# 201944AEP4P03.net
KiCad netlist of a schematic drawn in Altium Designer
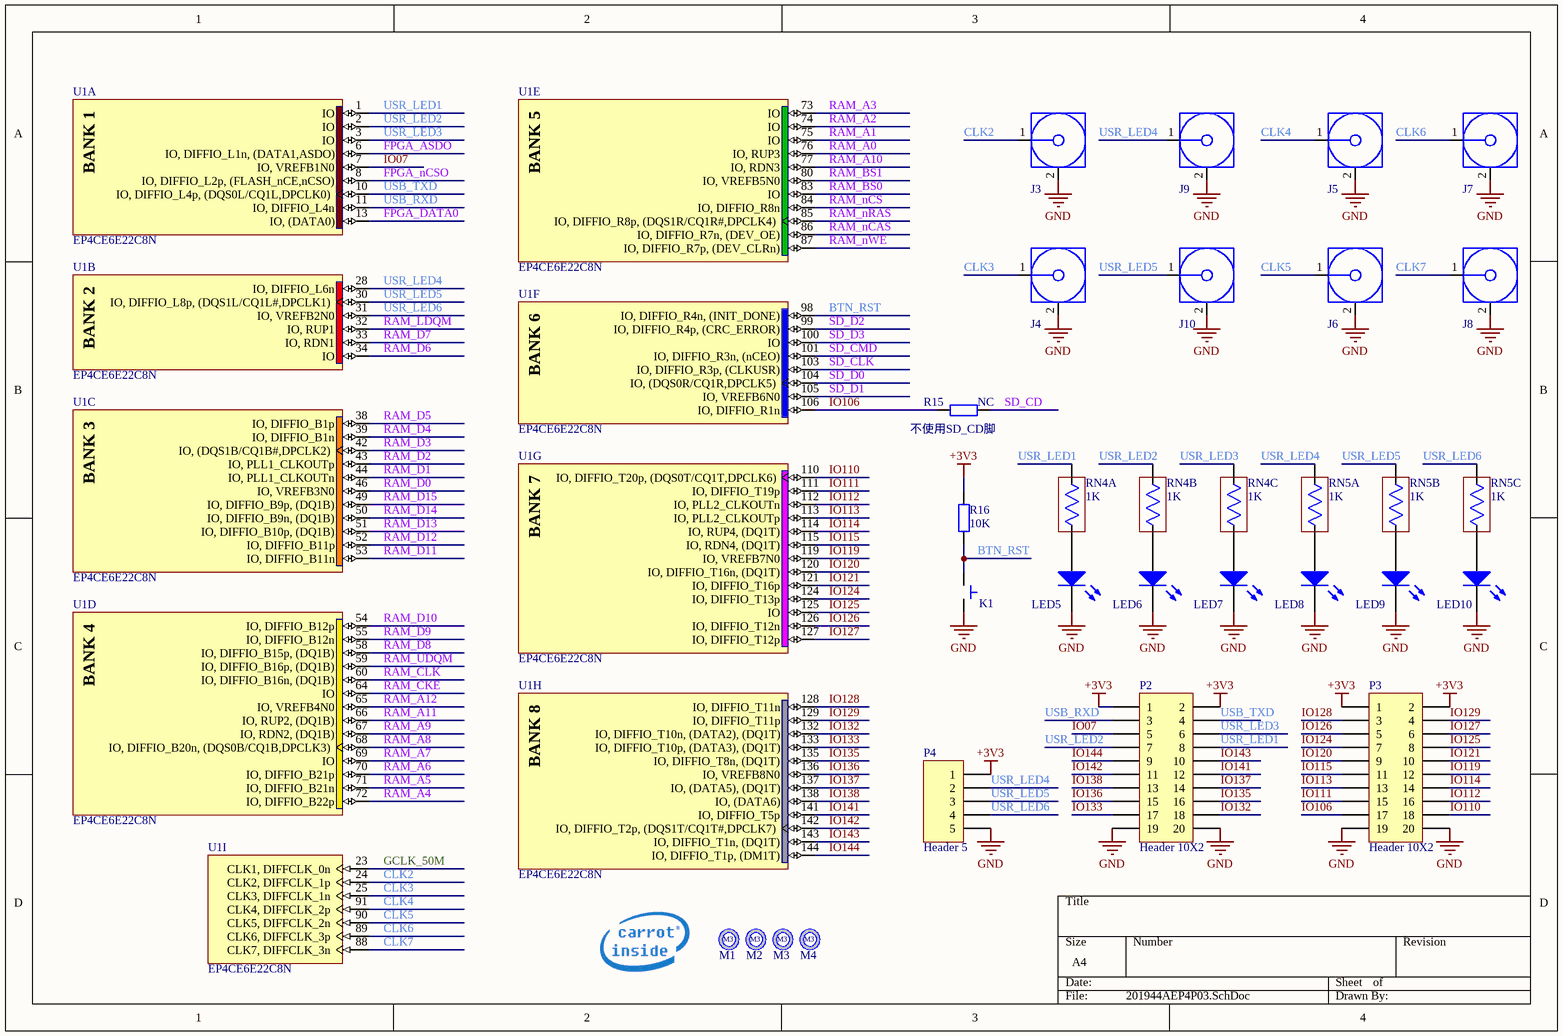
[diagram p0: 201944AEP4P03.SchDoc]

(export (version "E")
  (design (tool "Eeschema 10.0.6"))
  (components
    (comp (ref "J3") (value "SMA") (footprint "SMA-1") (libsource (lib "carrot_lib") (part "SMA")))
    (comp (ref "J4") (value "SMA") (footprint "SMA-1") (libsource (lib "carrot_lib") (part "SMA")))
    (comp (ref "J5") (value "SMA") (footprint "SMA-1") (libsource (lib "carrot_lib") (part "SMA")))
    (comp (ref "J6") (value "SMA") (footprint "SMA-1") (libsource (lib "carrot_lib") (part "SMA")))
    (comp (ref "J7") (value "SMA") (footprint "SMA-1") (libsource (lib "carrot_lib") (part "SMA")))
    (comp (ref "J8") (value "SMA") (footprint "SMA-1") (libsource (lib "carrot_lib") (part "SMA")))
    (comp (ref "J9") (value "SMA") (footprint "SMA-1") (libsource (lib "carrot_lib") (part "SMA")))
    (comp (ref "J10") (value "SMA") (footprint "SMA-1") (libsource (lib "carrot_lib") (part "SMA")))
    (comp (ref "K1")
      (value "轻触开关")
      (footprint "Button-SMT-Small")
      (libsource (lib "carrot_lib") (part "Button"))
    )
    (comp (ref "LED5") (value "LED") (footprint "LED1206") (libsource (lib "carrot_lib") (part "LED")))
    (comp (ref "LED6") (value "LED") (footprint "LED1206") (libsource (lib "carrot_lib") (part "LED")))
    (comp (ref "LED7") (value "LED") (footprint "LED1206") (libsource (lib "carrot_lib") (part "LED")))
    (comp (ref "LED8") (value "LED") (footprint "LED1206") (libsource (lib "carrot_lib") (part "LED")))
    (comp (ref "LED9") (value "LED") (footprint "LED1206") (libsource (lib "carrot_lib") (part "LED")))
    (comp (ref "LED10") (value "LED") (footprint "LED1206") (libsource (lib "carrot_lib") (part "LED")))
    (comp (ref "LOGO1")
      (value "Logo Carrot Inside")
      (footprint "LOGO-carrot-inside")
      (libsource (lib "carrot_lib") (part "Logo Carrot Inside"))
    )
    (comp (ref "M1") (value "M3") (footprint "M3-3.2X5") (libsource (lib "carrot_lib") (part "M3")))
    (comp (ref "M2") (value "M3") (footprint "M3-3.2X5") (libsource (lib "carrot_lib") (part "M3")))
    (comp (ref "M3") (value "M3") (footprint "M3-3.2X5") (libsource (lib "carrot_lib") (part "M3")))
    (comp (ref "M4") (value "M3") (footprint "M3-3.2X5") (libsource (lib "carrot_lib") (part "M3")))
    (comp (ref "P2")
      (value "Header 10X2")
      (footprint "HDR2X10")
      (description "Header, 10-Pin, Dual row")
      (fields (field (name "PUBLISHER") "Altium Limited"))
      (libsource (lib "Miscellaneous Connectors") (part "Header 10X2"))
    )
    (comp (ref "P3")
      (value "Header 10X2")
      (footprint "HDR2X10")
      (description "Header, 10-Pin, Dual row")
      (fields (field (name "PUBLISHER") "Altium Limited"))
      (libsource (lib "Miscellaneous Connectors") (part "Header 10X2"))
    )
    (comp (ref "P4")
      (value "Header 5")
      (footprint "HDR1X5")
      (description "Header, 5-Pin")
      (fields (field (name "PUBLISHER") "Altium Limited"))
      (libsource (lib "Miscellaneous Connectors") (part "Header 5"))
    )
    (comp (ref "R15")
      (value "NC")
      (footprint "R0805")
      (fields (field (name "Comment") "Res"))
      (libsource (lib "carrot_lib") (part "Res"))
    )
    (comp (ref "R16")
      (value "10K")
      (footprint "R0805")
      (fields (field (name "Comment") "Res"))
      (libsource (lib "") (part "Res_1"))
    )
    (comp (ref "RN4")
      (value "1K")
      (footprint "RA0603")
      (description "贴片排阻")
      (fields (field (name "Comment") "Res Array"))
      (libsource (lib "carrot_lib") (part "Res Array 2"))
    )
    (comp (ref "RN5")
      (value "1K")
      (footprint "RA0603")
      (description "贴片排阻")
      (fields (field (name "Comment") "Res Array"))
      (libsource (lib "carrot_lib") (part "Res Array 2"))
    )
    (comp (ref "U1")
      (value "EP4CE6E22C8N")
      (footprint "EP4CE6E22C8N-EQFP144+")
      (fields (field (name "MANUFACTURER") "Altera"))
      (libsource (lib "") (part "EP4CE6E22C8N_1"))
    )
  )
  (nets
    (net (code "1") (name "+3V3") (class "Default")
      (node (ref "P2") (pin "1") (pinfunction "1_1") (pintype "passive"))
      (node (ref "P2") (pin "2") (pinfunction "2_2") (pintype "passive"))
      (node (ref "P3") (pin "1") (pinfunction "1_1") (pintype "passive"))
      (node (ref "P3") (pin "2") (pinfunction "2_2") (pintype "passive"))
      (node (ref "P4") (pin "1") (pinfunction "1_1") (pintype "passive"))
      (node (ref "R16") (pin "1") (pinfunction "1_1") (pintype "passive"))
    )
    (net (code "2") (name "/BTN_RST") (class "Default")
      (node (ref "K1") (pin "1") (pinfunction "IN_1") (pintype "passive"))
      (node (ref "R16") (pin "2") (pinfunction "2_2") (pintype "passive"))
      (node (ref "U1") (pin "98") (pinfunction "IO,_DIFFIO_R4n,_(INIT_DONE)_98") (pintype "bidirectional"))
    )
    (net (code "3") (name "/CLK2") (class "Default")
      (node (ref "J3") (pin "1") (pinfunction "Signal_1") (pintype "power_in"))
      (node (ref "U1") (pin "24") (pinfunction "CLK2,_DIFFCLK_1p_24") (pintype "input"))
    )
    (net (code "4") (name "/CLK3") (class "Default")
      (node (ref "J4") (pin "1") (pinfunction "Signal_1") (pintype "power_in"))
      (node (ref "U1") (pin "25") (pinfunction "CLK3,_DIFFCLK_1n_25") (pintype "input"))
    )
    (net (code "5") (name "/CLK4") (class "Default")
      (node (ref "J5") (pin "1") (pinfunction "Signal_1") (pintype "power_in"))
      (node (ref "U1") (pin "91") (pinfunction "CLK4,_DIFFCLK_2p_91") (pintype "input"))
    )
    (net (code "6") (name "/CLK5") (class "Default")
      (node (ref "J6") (pin "1") (pinfunction "Signal_1") (pintype "power_in"))
      (node (ref "U1") (pin "90") (pinfunction "CLK5,_DIFFCLK_2n_90") (pintype "input"))
    )
    (net (code "7") (name "/CLK6") (class "Default")
      (node (ref "J7") (pin "1") (pinfunction "Signal_1") (pintype "power_in"))
      (node (ref "U1") (pin "89") (pinfunction "CLK6,_DIFFCLK_3p_89") (pintype "input"))
    )
    (net (code "8") (name "/CLK7") (class "Default")
      (node (ref "J8") (pin "1") (pinfunction "Signal_1") (pintype "power_in"))
      (node (ref "U1") (pin "88") (pinfunction "CLK7,_DIFFCLK_3n_88") (pintype "input"))
    )
    (net (code "9") (name "/FPGA_ASDO") (class "Default")
      (node (ref "U1") (pin "6") (pinfunction "IO,_DIFFIO_L1n,_(DATA1,ASDO)_6") (pintype "bidirectional"))
    )
    (net (code "10") (name "/FPGA_DATA0") (class "Default")
      (node (ref "U1") (pin "13") (pinfunction "IO,_(DATA0)_13") (pintype "bidirectional"))
    )
    (net (code "11") (name "/FPGA_nCSO") (class "Default")
      (node (ref "U1") (pin "8") (pinfunction "IO,_DIFFIO_L2p,_(FLASH_nCE,nCSO)_8") (pintype "bidirectional"))
    )
    (net (code "12") (name "/GCLK_50M") (class "Default")
      (node (ref "U1") (pin "23") (pinfunction "CLK1,_DIFFCLK_0n_23") (pintype "input"))
    )
    (net (code "13") (name "/IO07") (class "Default")
      (node (ref "P2") (pin "5") (pinfunction "5_5") (pintype "passive"))
      (node (ref "U1") (pin "7") (pinfunction "IO,_VREFB1N0_7") (pintype "bidirectional"))
    )
    (net (code "14") (name "/IO106") (class "Default")
      (node (ref "P3") (pin "17") (pinfunction "17_17") (pintype "passive"))
      (node (ref "R15") (pin "1") (pinfunction "1_1") (pintype "passive"))
      (node (ref "U1") (pin "106") (pinfunction "IO,_DIFFIO_R1n_106") (pintype "bidirectional"))
    )
    (net (code "15") (name "/IO110") (class "Default")
      (node (ref "P3") (pin "18") (pinfunction "18_18") (pintype "passive"))
      (node (ref "U1") (pin "110") (pinfunction "IO,_DIFFIO_T20p,_(DQS0T/CQ1T,DPCLK6)_110") (pintype "bidirectional"))
    )
    (net (code "16") (name "/IO111") (class "Default")
      (node (ref "P3") (pin "15") (pinfunction "15_15") (pintype "passive"))
      (node (ref "U1") (pin "111") (pinfunction "IO,_DIFFIO_T19p_111") (pintype "bidirectional"))
    )
    (net (code "17") (name "/IO112") (class "Default")
      (node (ref "P3") (pin "16") (pinfunction "16_16") (pintype "passive"))
      (node (ref "U1") (pin "112") (pinfunction "IO,_PLL2_CLKOUTn_112") (pintype "bidirectional"))
    )
    (net (code "18") (name "/IO113") (class "Default")
      (node (ref "P3") (pin "13") (pinfunction "13_13") (pintype "passive"))
      (node (ref "U1") (pin "113") (pinfunction "IO,_PLL2_CLKOUTp_113") (pintype "bidirectional"))
    )
    (net (code "19") (name "/IO114") (class "Default")
      (node (ref "P3") (pin "14") (pinfunction "14_14") (pintype "passive"))
      (node (ref "U1") (pin "114") (pinfunction "IO,_RUP4,_(DQ1T)_114") (pintype "bidirectional"))
    )
    (net (code "20") (name "/IO115") (class "Default")
      (node (ref "P3") (pin "11") (pinfunction "11_11") (pintype "passive"))
      (node (ref "U1") (pin "115") (pinfunction "IO,_RDN4,_(DQ1T)_115") (pintype "bidirectional"))
    )
    (net (code "21") (name "/IO119") (class "Default")
      (node (ref "P3") (pin "12") (pinfunction "12_12") (pintype "passive"))
      (node (ref "U1") (pin "119") (pinfunction "IO,_VREFB7N0_119") (pintype "bidirectional"))
    )
    (net (code "22") (name "/IO120") (class "Default")
      (node (ref "P3") (pin "9") (pinfunction "9_9") (pintype "passive"))
      (node (ref "U1") (pin "120") (pinfunction "IO,_DIFFIO_T16n,_(DQ1T)_120") (pintype "bidirectional"))
    )
    (net (code "23") (name "/IO121") (class "Default")
      (node (ref "P3") (pin "10") (pinfunction "10_10") (pintype "passive"))
      (node (ref "U1") (pin "121") (pinfunction "IO,_DIFFIO_T16p_121") (pintype "bidirectional"))
    )
    (net (code "24") (name "/IO124") (class "Default")
      (node (ref "P3") (pin "7") (pinfunction "7_7") (pintype "passive"))
      (node (ref "U1") (pin "124") (pinfunction "IO,_DIFFIO_T13p_124") (pintype "bidirectional"))
    )
    (net (code "25") (name "/IO125") (class "Default")
      (node (ref "P3") (pin "8") (pinfunction "8_8") (pintype "passive"))
      (node (ref "U1") (pin "125") (pinfunction "IO_125") (pintype "bidirectional"))
    )
    (net (code "26") (name "/IO126") (class "Default")
      (node (ref "P3") (pin "5") (pinfunction "5_5") (pintype "passive"))
      (node (ref "U1") (pin "126") (pinfunction "IO,_DIFFIO_T12n_126") (pintype "bidirectional"))
    )
    (net (code "27") (name "/IO127") (class "Default")
      (node (ref "P3") (pin "6") (pinfunction "6_6") (pintype "passive"))
      (node (ref "U1") (pin "127") (pinfunction "IO,_DIFFIO_T12p_127") (pintype "bidirectional"))
    )
    (net (code "28") (name "/IO128") (class "Default")
      (node (ref "P3") (pin "3") (pinfunction "3_3") (pintype "passive"))
      (node (ref "U1") (pin "128") (pinfunction "IO,_DIFFIO_T11n_128") (pintype "bidirectional"))
    )
    (net (code "29") (name "/IO129") (class "Default")
      (node (ref "P3") (pin "4") (pinfunction "4_4") (pintype "passive"))
      (node (ref "U1") (pin "129") (pinfunction "IO,_DIFFIO_T11p_129") (pintype "bidirectional"))
    )
    (net (code "30") (name "/IO132") (class "Default")
      (node (ref "P2") (pin "18") (pinfunction "18_18") (pintype "passive"))
      (node (ref "U1") (pin "132") (pinfunction "IO,_DIFFIO_T10n,_(DATA2),_(DQ1T)_132") (pintype "bidirectional"))
    )
    (net (code "31") (name "/IO133") (class "Default")
      (node (ref "P2") (pin "17") (pinfunction "17_17") (pintype "passive"))
      (node (ref "U1") (pin "133") (pinfunction "IO,_DIFFIO_T10p,_(DATA3),_(DQ1T)_133") (pintype "bidirectional"))
    )
    (net (code "32") (name "/IO135") (class "Default")
      (node (ref "P2") (pin "16") (pinfunction "16_16") (pintype "passive"))
      (node (ref "U1") (pin "135") (pinfunction "IO,_DIFFIO_T8n,_(DQ1T)_135") (pintype "bidirectional"))
    )
    (net (code "33") (name "/IO136") (class "Default")
      (node (ref "P2") (pin "15") (pinfunction "15_15") (pintype "passive"))
      (node (ref "U1") (pin "136") (pinfunction "IO,_VREFB8N0_136") (pintype "bidirectional"))
    )
    (net (code "34") (name "/IO137") (class "Default")
      (node (ref "P2") (pin "14") (pinfunction "14_14") (pintype "passive"))
      (node (ref "U1") (pin "137") (pinfunction "IO,_(DATA5),_(DQ1T)_137") (pintype "bidirectional"))
    )
    (net (code "35") (name "/IO138") (class "Default")
      (node (ref "P2") (pin "13") (pinfunction "13_13") (pintype "passive"))
      (node (ref "U1") (pin "138") (pinfunction "IO,_(DATA6)_138") (pintype "bidirectional"))
    )
    (net (code "36") (name "/IO141") (class "Default")
      (node (ref "P2") (pin "12") (pinfunction "12_12") (pintype "passive"))
      (node (ref "U1") (pin "141") (pinfunction "IO,_DIFFIO_T5p_141") (pintype "bidirectional"))
    )
    (net (code "37") (name "/IO142") (class "Default")
      (node (ref "P2") (pin "11") (pinfunction "11_11") (pintype "passive"))
      (node (ref "U1") (pin "142") (pinfunction "IO,_DIFFIO_T2p,_(DQS1T/CQ1T#,DPCLK7)_142") (pintype "bidirectional"))
    )
    (net (code "38") (name "/IO143") (class "Default")
      (node (ref "P2") (pin "10") (pinfunction "10_10") (pintype "passive"))
      (node (ref "U1") (pin "143") (pinfunction "IO,_DIFFIO_T1n,_(DQ1T)_143") (pintype "bidirectional"))
    )
    (net (code "39") (name "/IO144") (class "Default")
      (node (ref "P2") (pin "9") (pinfunction "9_9") (pintype "passive"))
      (node (ref "U1") (pin "144") (pinfunction "IO,_DIFFIO_T1p,_(DM1T)_144") (pintype "bidirectional"))
    )
    (net (code "40") (name "/RAM_A0") (class "Default")
      (node (ref "U1") (pin "76") (pinfunction "IO,_RUP3_76") (pintype "bidirectional"))
    )
    (net (code "41") (name "/RAM_A1") (class "Default")
      (node (ref "U1") (pin "75") (pinfunction "IO_75") (pintype "bidirectional"))
    )
    (net (code "42") (name "/RAM_A2") (class "Default")
      (node (ref "U1") (pin "74") (pinfunction "IO_74") (pintype "bidirectional"))
    )
    (net (code "43") (name "/RAM_A3") (class "Default")
      (node (ref "U1") (pin "73") (pinfunction "IO_73") (pintype "bidirectional"))
    )
    (net (code "44") (name "/RAM_A4") (class "Default")
      (node (ref "U1") (pin "72") (pinfunction "IO,_DIFFIO_B22p_72") (pintype "bidirectional"))
    )
    (net (code "45") (name "/RAM_A5") (class "Default")
      (node (ref "U1") (pin "71") (pinfunction "IO,_DIFFIO_B21n_71") (pintype "bidirectional"))
    )
    (net (code "46") (name "/RAM_A6") (class "Default")
      (node (ref "U1") (pin "70") (pinfunction "IO,_DIFFIO_B21p_70") (pintype "bidirectional"))
    )
    (net (code "47") (name "/RAM_A7") (class "Default")
      (node (ref "U1") (pin "69") (pinfunction "IO_69") (pintype "bidirectional"))
    )
    (net (code "48") (name "/RAM_A8") (class "Default")
      (node (ref "U1") (pin "68") (pinfunction "IO,_DIFFIO_B20n,_(DQS0B/CQ1B,DPCLK3)_68") (pintype "bidirectional"))
    )
    (net (code "49") (name "/RAM_A9") (class "Default")
      (node (ref "U1") (pin "67") (pinfunction "IO,_RDN2,_(DQ1B)_67") (pintype "bidirectional"))
    )
    (net (code "50") (name "/RAM_A10") (class "Default")
      (node (ref "U1") (pin "77") (pinfunction "IO,_RDN3_77") (pintype "bidirectional"))
    )
    (net (code "51") (name "/RAM_A11") (class "Default")
      (node (ref "U1") (pin "66") (pinfunction "IO,_RUP2,_(DQ1B)_66") (pintype "bidirectional"))
    )
    (net (code "52") (name "/RAM_A12") (class "Default")
      (node (ref "U1") (pin "65") (pinfunction "IO,_VREFB4N0_65") (pintype "bidirectional"))
    )
    (net (code "53") (name "/RAM_BS0") (class "Default")
      (node (ref "U1") (pin "83") (pinfunction "IO_83") (pintype "bidirectional"))
    )
    (net (code "54") (name "/RAM_BS1") (class "Default")
      (node (ref "U1") (pin "80") (pinfunction "IO,_VREFB5N0_80") (pintype "bidirectional"))
    )
    (net (code "55") (name "/RAM_CKE") (class "Default")
      (node (ref "U1") (pin "64") (pinfunction "IO_64") (pintype "bidirectional"))
    )
    (net (code "56") (name "/RAM_CLK") (class "Default")
      (node (ref "U1") (pin "60") (pinfunction "IO,_DIFFIO_B16n,_(DQ1B)_60") (pintype "bidirectional"))
    )
    (net (code "57") (name "/RAM_D0") (class "Default")
      (node (ref "U1") (pin "46") (pinfunction "IO,_VREFB3N0_46") (pintype "bidirectional"))
    )
    (net (code "58") (name "/RAM_D1") (class "Default")
      (node (ref "U1") (pin "44") (pinfunction "IO,_PLL1_CLKOUTn_44") (pintype "bidirectional"))
    )
    (net (code "59") (name "/RAM_D2") (class "Default")
      (node (ref "U1") (pin "43") (pinfunction "IO,_PLL1_CLKOUTp_43") (pintype "bidirectional"))
    )
    (net (code "60") (name "/RAM_D3") (class "Default")
      (node (ref "U1") (pin "42") (pinfunction "IO,_(DQS1B/CQ1B#,DPCLK2)_42") (pintype "bidirectional"))
    )
    (net (code "61") (name "/RAM_D4") (class "Default")
      (node (ref "U1") (pin "39") (pinfunction "IO,_DIFFIO_B1n_39") (pintype "bidirectional"))
    )
    (net (code "62") (name "/RAM_D5") (class "Default")
      (node (ref "U1") (pin "38") (pinfunction "IO,_DIFFIO_B1p_38") (pintype "bidirectional"))
    )
    (net (code "63") (name "/RAM_D6") (class "Default")
      (node (ref "U1") (pin "34") (pinfunction "IO_34") (pintype "bidirectional"))
    )
    (net (code "64") (name "/RAM_D7") (class "Default")
      (node (ref "U1") (pin "33") (pinfunction "IO,_RDN1_33") (pintype "bidirectional"))
    )
    (net (code "65") (name "/RAM_D8") (class "Default")
      (node (ref "U1") (pin "58") (pinfunction "IO,_DIFFIO_B15p,_(DQ1B)_58") (pintype "bidirectional"))
    )
    (net (code "66") (name "/RAM_D9") (class "Default")
      (node (ref "U1") (pin "55") (pinfunction "IO,_DIFFIO_B12n_55") (pintype "bidirectional"))
    )
    (net (code "67") (name "/RAM_D10") (class "Default")
      (node (ref "U1") (pin "54") (pinfunction "IO,_DIFFIO_B12p_54") (pintype "bidirectional"))
    )
    (net (code "68") (name "/RAM_D11") (class "Default")
      (node (ref "U1") (pin "53") (pinfunction "IO,_DIFFIO_B11n_53") (pintype "bidirectional"))
    )
    (net (code "69") (name "/RAM_D12") (class "Default")
      (node (ref "U1") (pin "52") (pinfunction "IO,_DIFFIO_B11p_52") (pintype "bidirectional"))
    )
    (net (code "70") (name "/RAM_D13") (class "Default")
      (node (ref "U1") (pin "51") (pinfunction "IO,_DIFFIO_B10p,_(DQ1B)_51") (pintype "bidirectional"))
    )
    (net (code "71") (name "/RAM_D14") (class "Default")
      (node (ref "U1") (pin "50") (pinfunction "IO,_DIFFIO_B9n,_(DQ1B)_50") (pintype "bidirectional"))
    )
    (net (code "72") (name "/RAM_D15") (class "Default")
      (node (ref "U1") (pin "49") (pinfunction "IO,_DIFFIO_B9p,_(DQ1B)_49") (pintype "bidirectional"))
    )
    (net (code "73") (name "/RAM_LDQM") (class "Default")
      (node (ref "U1") (pin "32") (pinfunction "IO,_RUP1_32") (pintype "bidirectional"))
    )
    (net (code "74") (name "/RAM_UDQM") (class "Default")
      (node (ref "U1") (pin "59") (pinfunction "IO,_DIFFIO_B16p,_(DQ1B)_59") (pintype "bidirectional"))
    )
    (net (code "75") (name "/RAM_nCAS") (class "Default")
      (node (ref "U1") (pin "86") (pinfunction "IO,_DIFFIO_R7n,_(DEV_OE)_86") (pintype "bidirectional"))
    )
    (net (code "76") (name "/RAM_nCS") (class "Default")
      (node (ref "U1") (pin "84") (pinfunction "IO,_DIFFIO_R8n_84") (pintype "bidirectional"))
    )
    (net (code "77") (name "/RAM_nRAS") (class "Default")
      (node (ref "U1") (pin "85") (pinfunction "IO,_DIFFIO_R8p,_(DQS1R/CQ1R#,DPCLK4)_85") (pintype "bidirectional"))
    )
    (net (code "78") (name "/RAM_nWE") (class "Default")
      (node (ref "U1") (pin "87") (pinfunction "IO,_DIFFIO_R7p,_(DEV_CLRn)_87") (pintype "bidirectional"))
    )
    (net (code "79") (name "/SD_CD") (class "Default")
      (node (ref "R15") (pin "2") (pinfunction "2_2") (pintype "passive"))
    )
    (net (code "80") (name "/SD_CLK") (class "Default")
      (node (ref "U1") (pin "103") (pinfunction "IO,_DIFFIO_R3p,_(CLKUSR)_103") (pintype "bidirectional"))
    )
    (net (code "81") (name "/SD_CMD") (class "Default")
      (node (ref "U1") (pin "101") (pinfunction "IO,_DIFFIO_R3n,_(nCEO)_101") (pintype "bidirectional"))
    )
    (net (code "82") (name "/SD_D0") (class "Default")
      (node (ref "U1") (pin "104") (pinfunction "IO,_(DQS0R/CQ1R,DPCLK5)_104") (pintype "bidirectional"))
    )
    (net (code "83") (name "/SD_D1") (class "Default")
      (node (ref "U1") (pin "105") (pinfunction "IO,_VREFB6N0_105") (pintype "bidirectional"))
    )
    (net (code "84") (name "/SD_D2") (class "Default")
      (node (ref "U1") (pin "99") (pinfunction "IO,_DIFFIO_R4p,_(CRC_ERROR)_99") (pintype "bidirectional"))
    )
    (net (code "85") (name "/SD_D3") (class "Default")
      (node (ref "U1") (pin "100") (pinfunction "IO_100") (pintype "bidirectional"))
    )
    (net (code "86") (name "/USB_RXD") (class "Default")
      (node (ref "P2") (pin "3") (pinfunction "3_3") (pintype "passive"))
      (node (ref "U1") (pin "11") (pinfunction "IO,_DIFFIO_L4n_11") (pintype "bidirectional"))
    )
    (net (code "87") (name "/USB_TXD") (class "Default")
      (node (ref "P2") (pin "4") (pinfunction "4_4") (pintype "passive"))
      (node (ref "U1") (pin "10") (pinfunction "IO,_DIFFIO_L4p,_(DQS0L/CQ1L,DPCLK0)_10") (pintype "bidirectional"))
    )
    (net (code "88") (name "/USR_LED1") (class "Default")
      (node (ref "P2") (pin "8") (pinfunction "8_8") (pintype "passive"))
      (node (ref "RN4") (pin "8") (pinfunction "8_8") (pintype "passive"))
      (node (ref "U1") (pin "1") (pinfunction "IO_1") (pintype "bidirectional"))
    )
    (net (code "89") (name "/USR_LED2") (class "Default")
      (node (ref "P2") (pin "7") (pinfunction "7_7") (pintype "passive"))
      (node (ref "RN4") (pin "7") (pinfunction "7_7") (pintype "passive"))
      (node (ref "U1") (pin "2") (pinfunction "IO_2") (pintype "bidirectional"))
    )
    (net (code "90") (name "/USR_LED3") (class "Default")
      (node (ref "P2") (pin "6") (pinfunction "6_6") (pintype "passive"))
      (node (ref "RN4") (pin "6") (pinfunction "6_6") (pintype "passive"))
      (node (ref "U1") (pin "3") (pinfunction "IO_3") (pintype "bidirectional"))
    )
    (net (code "91") (name "/USR_LED4") (class "Default")
      (node (ref "J9") (pin "1") (pinfunction "Signal_1") (pintype "power_in"))
      (node (ref "P4") (pin "2") (pinfunction "2_2") (pintype "passive"))
      (node (ref "RN5") (pin "8") (pinfunction "8_8") (pintype "passive"))
      (node (ref "U1") (pin "28") (pinfunction "IO,_DIFFIO_L6n_28") (pintype "bidirectional"))
    )
    (net (code "92") (name "/USR_LED5") (class "Default")
      (node (ref "J10") (pin "1") (pinfunction "Signal_1") (pintype "power_in"))
      (node (ref "P4") (pin "3") (pinfunction "3_3") (pintype "passive"))
      (node (ref "RN5") (pin "7") (pinfunction "7_7") (pintype "passive"))
      (node (ref "U1") (pin "30") (pinfunction "IO,_DIFFIO_L8p,_(DQS1L/CQ1L#,DPCLK1)_30") (pintype "bidirectional"))
    )
    (net (code "93") (name "/USR_LED6") (class "Default")
      (node (ref "P4") (pin "4") (pinfunction "4_4") (pintype "passive"))
      (node (ref "RN5") (pin "6") (pinfunction "6_6") (pintype "passive"))
      (node (ref "U1") (pin "31") (pinfunction "IO,_VREFB2N0_31") (pintype "bidirectional"))
    )
    (net (code "94") (name "GND") (class "Default")
      (node (ref "J10") (pin "2") (pinfunction "GND_2") (pintype "power_in"))
      (node (ref "J3") (pin "2") (pinfunction "GND_2") (pintype "power_in"))
      (node (ref "J4") (pin "2") (pinfunction "GND_2") (pintype "power_in"))
      (node (ref "J5") (pin "2") (pinfunction "GND_2") (pintype "power_in"))
      (node (ref "J6") (pin "2") (pinfunction "GND_2") (pintype "power_in"))
      (node (ref "J7") (pin "2") (pinfunction "GND_2") (pintype "power_in"))
      (node (ref "J8") (pin "2") (pinfunction "GND_2") (pintype "power_in"))
      (node (ref "J9") (pin "2") (pinfunction "GND_2") (pintype "power_in"))
      (node (ref "K1") (pin "2") (pinfunction "OUT_2") (pintype "passive"))
      (node (ref "LED10") (pin "2") (pinfunction "K_2") (pintype "passive"))
      (node (ref "LED5") (pin "2") (pinfunction "K_2") (pintype "passive"))
      (node (ref "LED6") (pin "2") (pinfunction "K_2") (pintype "passive"))
      (node (ref "LED7") (pin "2") (pinfunction "K_2") (pintype "passive"))
      (node (ref "LED8") (pin "2") (pinfunction "K_2") (pintype "passive"))
      (node (ref "LED9") (pin "2") (pinfunction "K_2") (pintype "passive"))
      (node (ref "P2") (pin "19") (pinfunction "19_19") (pintype "passive"))
      (node (ref "P2") (pin "20") (pinfunction "20_20") (pintype "passive"))
      (node (ref "P3") (pin "19") (pinfunction "19_19") (pintype "passive"))
      (node (ref "P3") (pin "20") (pinfunction "20_20") (pintype "passive"))
      (node (ref "P4") (pin "5") (pinfunction "5_5") (pintype "passive"))
    )
    (net (code "95") (name "Net-(LED5-A)") (class "Default")
      (node (ref "LED5") (pin "1") (pinfunction "A_1") (pintype "passive"))
      (node (ref "RN4") (pin "1") (pinfunction "1_1") (pintype "passive"))
    )
    (net (code "96") (name "Net-(LED6-A)") (class "Default")
      (node (ref "LED6") (pin "1") (pinfunction "A_1") (pintype "passive"))
      (node (ref "RN4") (pin "2") (pinfunction "2_2") (pintype "passive"))
    )
    (net (code "97") (name "Net-(LED7-A)") (class "Default")
      (node (ref "LED7") (pin "1") (pinfunction "A_1") (pintype "passive"))
      (node (ref "RN4") (pin "3") (pinfunction "3_3") (pintype "passive"))
    )
    (net (code "98") (name "Net-(LED8-A)") (class "Default")
      (node (ref "LED8") (pin "1") (pinfunction "A_1") (pintype "passive"))
      (node (ref "RN5") (pin "1") (pinfunction "1_1") (pintype "passive"))
    )
    (net (code "99") (name "Net-(LED9-A)") (class "Default")
      (node (ref "LED9") (pin "1") (pinfunction "A_1") (pintype "passive"))
      (node (ref "RN5") (pin "2") (pinfunction "2_2") (pintype "passive"))
    )
    (net (code "100") (name "Net-(LED10-A)") (class "Default")
      (node (ref "LED10") (pin "1") (pinfunction "A_1") (pintype "passive"))
      (node (ref "RN5") (pin "3") (pinfunction "3_3") (pintype "passive"))
    )
  )
)
